# Sheet1.net
KiCad netlist of a schematic drawn in Altium Designer
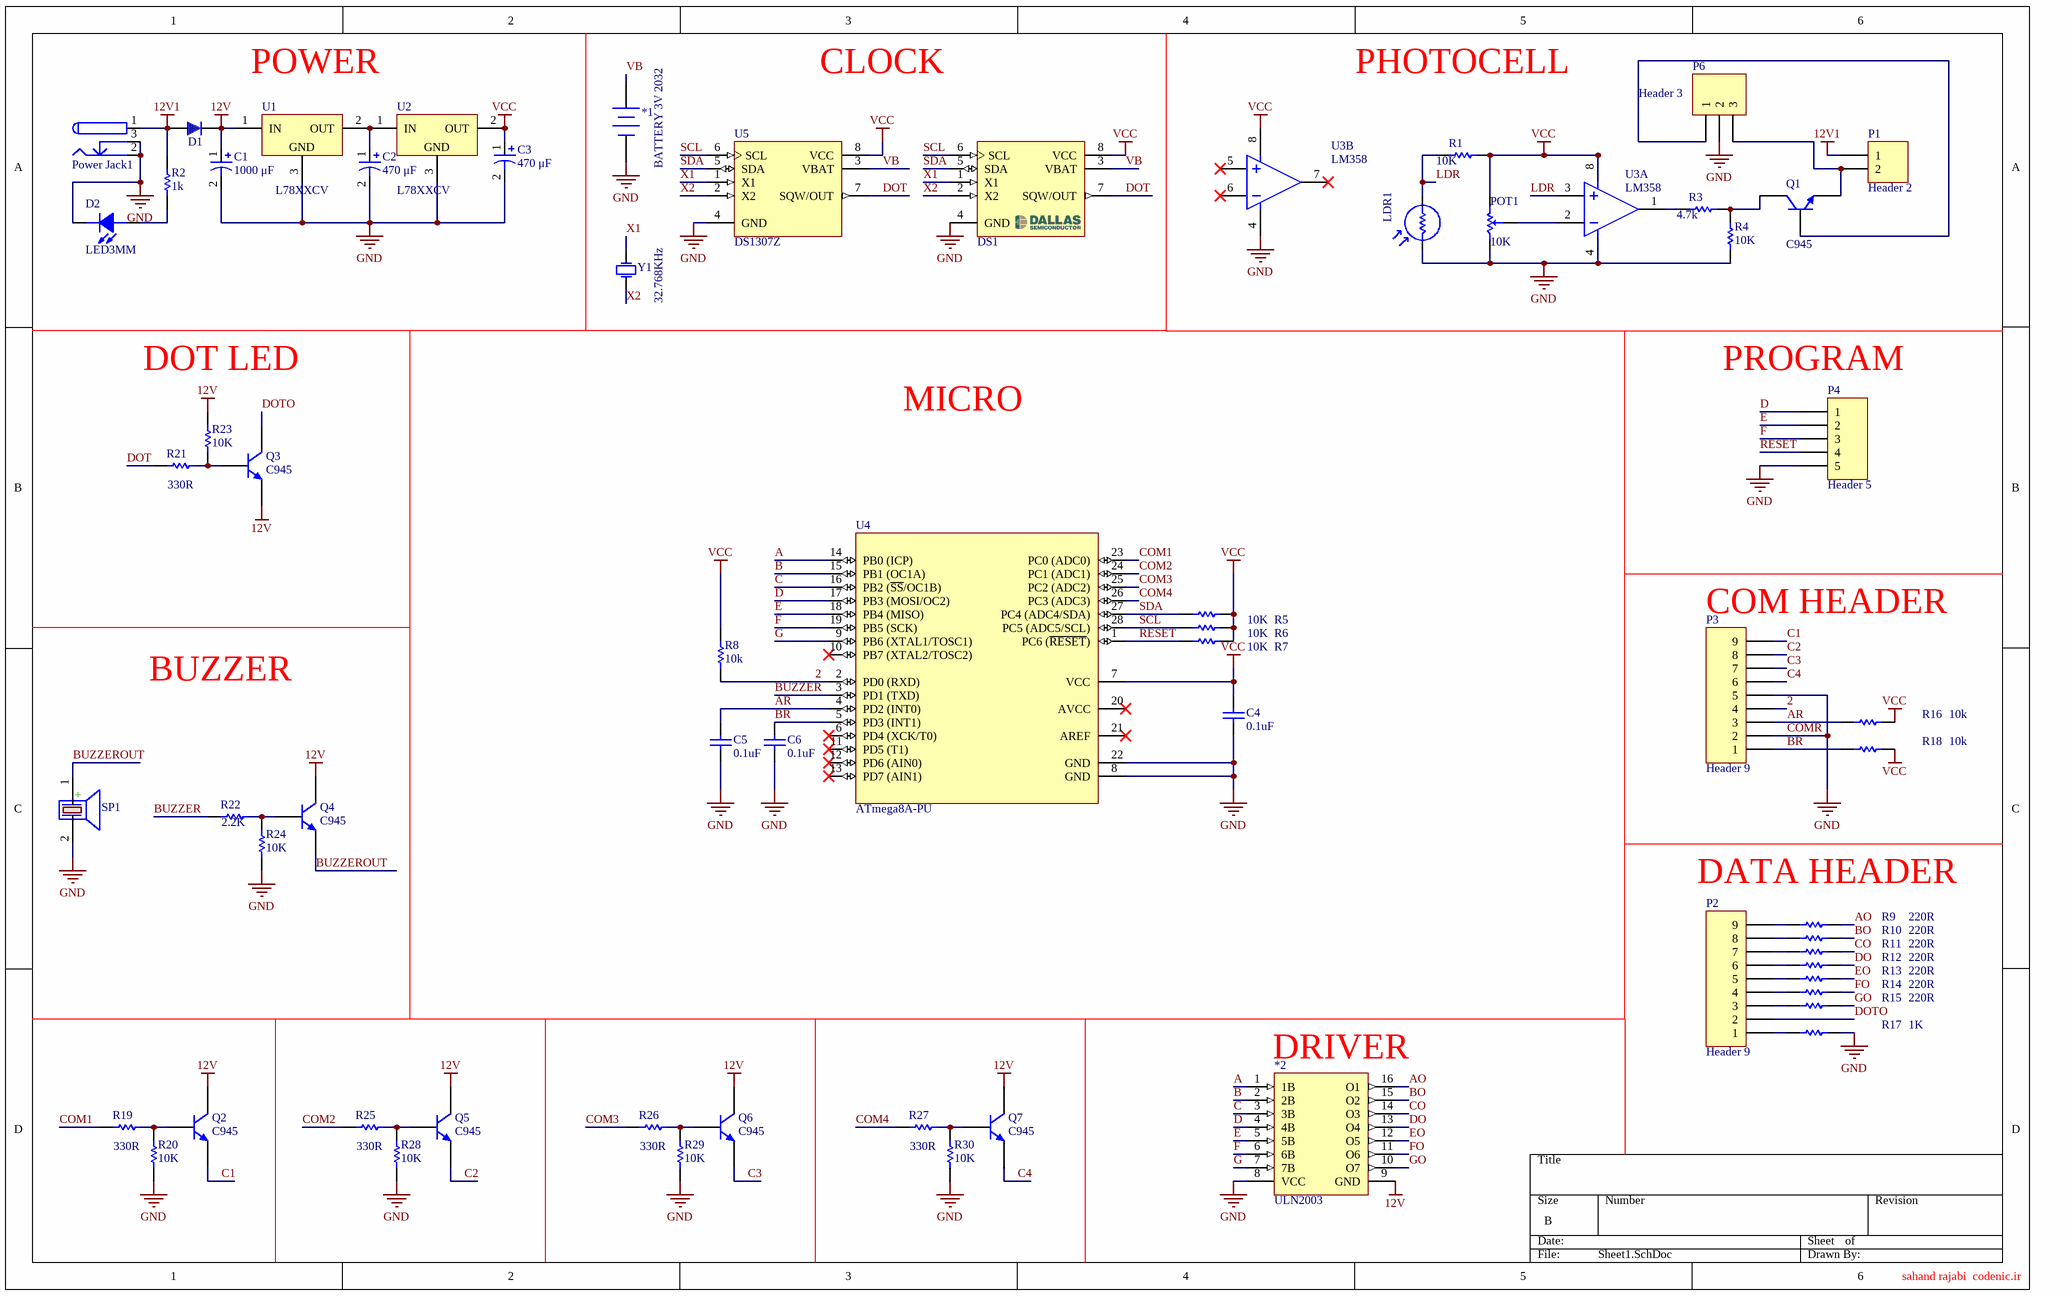
[diagram p0: Sheet1.SchDoc]

(export (version "E")
  (design (tool "Eeschema 10.0.6"))
  (components
    (comp (ref "*1")
      (value "BATTERY 3V 2032")
      (footprint "batt")
      (libsource (lib "General_04") (part "BATTERY 3V 2032"))
    )
    (comp (ref "*2") (value "ULN2003") (footprint "ULN2003") (libsource (lib "General_04") (part "ULN2003")))
    (comp (ref "C1")
      (value "1000 μF")
      (footprint "WCAP-PTHT 8x11.5x3.5x0.6")
      (description "WCAP-PTHT Aluminum Polymer Capacitors , 1000 μF; + / - 20%; 6,3 V , 8 x 11,5")
      (fields
        (field (name "MANUFACTURER") "Wurth Elektronik")
        (field (name "PARTNO") "870135174006")
        (field (name "E-MAIL") "libraries@we-online.com")
        (field (name "CREATED BY") "Karrer Zheng")
      )
      (libsource (lib "Capacitor_13 WCAP-PTHT_rev15a") (part "WCAP-PTHT 8x11.5x3.5x0.6 870135174006"))
    )
    (comp (ref "C2")
      (value "470 μF")
      (footprint "WCAP-PTHT 8x8x3.5x0.6")
      (description "WCAP-PTHT Aluminum Polymer Capacitors , 470 μF; + / - 20%; 6,3 V , 8 x 8")
      (fields
        (field (name "MANUFACTURER") "Wurth Elektronik")
        (field (name "PARTNO") "870135174002")
        (field (name "E-MAIL") "libraries@we-online.com")
        (field (name "CREATED BY") "Karrer Zheng")
      )
      (libsource (lib "Capacitor_13 WCAP-PTHT_rev15a") (part "WCAP-PTHT 8x8x3.5x0.6 870135174002"))
    )
    (comp (ref "C3")
      (value "470 μF")
      (footprint "WCAP-PTHT 8x8x3.5x0.6")
      (description "WCAP-PTHT Aluminum Polymer Capacitors , 470 μF; + / - 20%; 6,3 V , 8 x 8")
      (fields
        (field (name "MANUFACTURER") "Wurth Elektronik")
        (field (name "PARTNO") "870135174002")
        (field (name "E-MAIL") "libraries@we-online.com")
        (field (name "CREATED BY") "Karrer Zheng")
      )
      (libsource (lib "Capacitor_13 WCAP-PTHT_rev15a") (part "WCAP-PTHT 8x8x3.5x0.6 870135174002"))
    )
    (comp (ref "C4")
      (value "0.1uF")
      (footprint "CAPC4817X12N")
      (description "CAP 1206")
      (fields (field (name "DESIGNER") "Abbas Basereh"))
      (libsource (lib "Altium") (part "CAP SMD 1206"))
    )
    (comp (ref "C5")
      (value "0.1uF")
      (footprint "CAPC4817X12N")
      (description "CAP 1206")
      (fields (field (name "DESIGNER") "Abbas Basereh"))
      (libsource (lib "Altium") (part "CAP SMD 1206"))
    )
    (comp (ref "C6")
      (value "0.1uF")
      (footprint "CAPC4817X12N")
      (description "CAP 1206")
      (fields (field (name "DESIGNER") "Abbas Basereh"))
      (libsource (lib "Altium") (part "CAP SMD 1206"))
    )
    (comp (ref "D1")
      (value "1n4007")
      (footprint "DIOM4629X24N")
      (description "Standard Rectifiers")
      (fields (field (name "MANUFACTURER") "DC COMPONENTS") (field (name "DESIGNER") "Abbas Basereh"))
      (libsource (lib "Altium") (part "1n4007 SMD M7"))
    )
    (comp (ref "D2")
      (value "LED3MM")
      (footprint "LED3mm_GRN")
      (description "Light Emitting Diode")
      (fields (field (name "DESIGNER") "Ali Hafizi"))
      (libsource (lib "Altium") (part "LED 3MM"))
    )
    (comp (ref "DS1")
      (value "DS1307")
      (footprint "DIP_8")
      (fields (field (name "PUBLISHER") "Altium Limited"))
      (libsource (lib "General_10") (part "DS1307."))
    )
    (comp (ref "LDR1")
      (value "PhotoCell")
      (footprint "PhotoCell")
      (description "Photo Cell- Variable Resistor With Light")
      (fields (field (name "DESIGNER") "Saeid Jorablo"))
      (libsource (lib "Altium") (part "LDR"))
    )
    (comp (ref "P1")
      (value "Header 2")
      (footprint "HDR1X2")
      (description "Header, 2-Pin")
      (fields (field (name "PUBLISHER") "Altium Limited"))
      (libsource (lib "Altium") (part "Header 2"))
    )
    (comp (ref "P2")
      (value "Header 9")
      (footprint "HDR1X9")
      (description "Header, 9-Pin")
      (fields (field (name "PUBLISHER") "Altium Limited"))
      (libsource (lib "Altium") (part "Header 9"))
    )
    (comp (ref "P3")
      (value "Header 9")
      (footprint "HDR1X9")
      (description "Header, 9-Pin")
      (fields (field (name "PUBLISHER") "Altium Limited"))
      (libsource (lib "Altium") (part "Header 9"))
    )
    (comp (ref "P4")
      (value "Header 5")
      (footprint "HDR1X5")
      (description "Header, 5-Pin")
      (fields (field (name "PUBLISHER") "Altium Limited"))
      (libsource (lib "Altium") (part "Header 5"))
    )
    (comp (ref "P6")
      (value "Header 3")
      (footprint "HDR1X3")
      (description "Header, 3-Pin")
      (fields (field (name "PUBLISHER") "Altium Limited"))
      (libsource (lib "Miscellaneous Connectors") (part "Header 3"))
    )
    (comp (ref "POT1")
      (value "10K")
      (footprint "POT 4")
      (description "Variable Resistor")
      (libsource (lib "Altium") (part "POT"))
    )
    (comp (ref "Power Jack1")
      (value "Power Jack.")
      (footprint "Power Jack.")
      (libsource (lib "General_10") (part "Power Jack."))
    )
    (comp (ref "Q1")
      (value "C945")
      (footprint "c945")
      (description "NPN Silicon Epitaxial Planar Transistor")
      (fields (field (name "PUBLISHER") "Abbas Basereh"))
      (libsource (lib "Altium") (part "C945"))
    )
    (comp (ref "Q2")
      (value "C945")
      (footprint "C945")
      (description "NPN Transistor")
      (fields (field (name "DESIGNER") "Saeid Jorablo"))
      (libsource (lib "My Library1111") (part "C945"))
    )
    (comp (ref "Q3")
      (value "C945")
      (footprint "C945")
      (description "NPN Transistor")
      (fields (field (name "DESIGNER") "Saeid Jorablo"))
      (libsource (lib "My Library1111") (part "C945"))
    )
    (comp (ref "Q4")
      (value "C945")
      (footprint "C945")
      (description "NPN Transistor")
      (fields (field (name "DESIGNER") "Saeid Jorablo"))
      (libsource (lib "My Library1111") (part "C945"))
    )
    (comp (ref "Q5")
      (value "C945")
      (footprint "C945")
      (description "NPN Transistor")
      (fields (field (name "DESIGNER") "Saeid Jorablo"))
      (libsource (lib "My Library1111") (part "C945"))
    )
    (comp (ref "Q6")
      (value "C945")
      (footprint "C945")
      (description "NPN Transistor")
      (fields (field (name "DESIGNER") "Saeid Jorablo"))
      (libsource (lib "My Library1111") (part "C945"))
    )
    (comp (ref "Q7")
      (value "C945")
      (footprint "C945")
      (description "NPN Transistor")
      (fields (field (name "DESIGNER") "Saeid Jorablo"))
      (libsource (lib "My Library1111") (part "C945"))
    )
    (comp (ref "R1")
      (value "10K")
      (footprint "Resistor_SMD_1206")
      (description "Resistor 0.25w")
      (fields (field (name "PUBLISHER") "Altium Limited"))
      (libsource (lib "General_10") (part "Resistor"))
    )
    (comp (ref "R2")
      (value "1k")
      (footprint "Resistor_SMD_1206")
      (description "Resistor 0.25w")
      (fields (field (name "PUBLISHER") "Altium Limited"))
      (libsource (lib "General_10") (part "Resistor"))
    )
    (comp (ref "R3")
      (value "4.7k")
      (footprint "Resistor_SMD_1206")
      (description "Resistor 0.25w")
      (fields (field (name "PUBLISHER") "Altium Limited"))
      (libsource (lib "General_10") (part "Resistor"))
    )
    (comp (ref "R4")
      (value "10K")
      (footprint "Resistor_SMD_1206")
      (description "Resistor 0.25w")
      (fields (field (name "PUBLISHER") "Altium Limited"))
      (libsource (lib "General_10") (part "Resistor"))
    )
    (comp (ref "R5")
      (value "10K")
      (footprint "Resistor_SMD_1206")
      (description "Resistor 0.25w")
      (fields (field (name "PUBLISHER") "Altium Limited"))
      (libsource (lib "General_10") (part "Resistor"))
    )
    (comp (ref "R6")
      (value "10K")
      (footprint "Resistor_SMD_1206")
      (description "Resistor 0.25w")
      (fields (field (name "PUBLISHER") "Altium Limited"))
      (libsource (lib "General_10") (part "Resistor"))
    )
    (comp (ref "R7")
      (value "10K")
      (footprint "Resistor_SMD_1206")
      (description "Resistor 0.25w")
      (fields (field (name "PUBLISHER") "Altium Limited"))
      (libsource (lib "General_10") (part "Resistor"))
    )
    (comp (ref "R8")
      (value "10k")
      (footprint "Resistor_SMD_1206")
      (description "Resistor 0.25w")
      (fields (field (name "PUBLISHER") "Altium Limited"))
      (libsource (lib "General_10") (part "Resistor"))
    )
    (comp (ref "R9")
      (value "220R")
      (footprint "Resistor_SMD_1206")
      (description "Resistor 0.25w")
      (fields (field (name "PUBLISHER") "Altium Limited"))
      (libsource (lib "General_10") (part "Resistor"))
    )
    (comp (ref "R10")
      (value "220R")
      (footprint "Resistor_SMD_1206")
      (description "Resistor 0.25w")
      (fields (field (name "PUBLISHER") "Altium Limited"))
      (libsource (lib "General_10") (part "Resistor"))
    )
    (comp (ref "R11")
      (value "220R")
      (footprint "Resistor_SMD_1206")
      (description "Resistor 0.25w")
      (fields (field (name "PUBLISHER") "Altium Limited"))
      (libsource (lib "General_10") (part "Resistor"))
    )
    (comp (ref "R12")
      (value "220R")
      (footprint "Resistor_SMD_1206")
      (description "Resistor 0.25w")
      (fields (field (name "PUBLISHER") "Altium Limited"))
      (libsource (lib "General_10") (part "Resistor"))
    )
    (comp (ref "R13")
      (value "220R")
      (footprint "Resistor_SMD_1206")
      (description "Resistor 0.25w")
      (fields (field (name "PUBLISHER") "Altium Limited"))
      (libsource (lib "General_10") (part "Resistor"))
    )
    (comp (ref "R14")
      (value "220R")
      (footprint "Resistor_SMD_1206")
      (description "Resistor 0.25w")
      (fields (field (name "PUBLISHER") "Altium Limited"))
      (libsource (lib "General_10") (part "Resistor"))
    )
    (comp (ref "R15")
      (value "220R")
      (footprint "Resistor_SMD_1206")
      (description "Resistor 0.25w")
      (fields (field (name "PUBLISHER") "Altium Limited"))
      (libsource (lib "General_10") (part "Resistor"))
    )
    (comp (ref "R16")
      (value "10k")
      (footprint "Resistor_SMD_1206")
      (description "Resistor 0.25w")
      (fields (field (name "PUBLISHER") "Altium Limited"))
      (libsource (lib "General_10") (part "Resistor"))
    )
    (comp (ref "R17")
      (value "1K")
      (footprint "Resistor_SMD_1206")
      (description "Resistor 0.25w")
      (fields (field (name "PUBLISHER") "Altium Limited"))
      (libsource (lib "General_10") (part "Resistor"))
    )
    (comp (ref "R18")
      (value "10k")
      (footprint "Resistor_SMD_1206")
      (description "Resistor 0.25w")
      (fields (field (name "PUBLISHER") "Altium Limited"))
      (libsource (lib "General_10") (part "Resistor"))
    )
    (comp (ref "R19")
      (value "330R")
      (footprint "RESC3413X04N")
      (description "RES 0805")
      (fields (field (name "DESIGNER") "Abbas Basereh"))
      (libsource (lib "2017AbbasBasereh9365731239 -ver1") (part "RES 0805 0.125W"))
    )
    (comp (ref "R20")
      (value "10K")
      (footprint "RESC3413X04N")
      (description "RES 0805")
      (fields (field (name "DESIGNER") "Abbas Basereh"))
      (libsource (lib "2017AbbasBasereh9365731239 -ver1") (part "RES 0805 0.125W"))
    )
    (comp (ref "R21")
      (value "330R")
      (footprint "RESC3413X04N")
      (description "RES 0805")
      (fields (field (name "DESIGNER") "Abbas Basereh"))
      (libsource (lib "2017AbbasBasereh9365731239 -ver1") (part "RES 0805 0.125W"))
    )
    (comp (ref "R22")
      (value "2.2K")
      (footprint "RESC3413X04N")
      (description "RES 0805")
      (fields (field (name "DESIGNER") "Abbas Basereh"))
      (libsource (lib "2017AbbasBasereh9365731239 -ver1") (part "RES 0805 0.125W"))
    )
    (comp (ref "R23")
      (value "10K")
      (footprint "RESC3413X04N")
      (description "RES 0805")
      (fields (field (name "DESIGNER") "Abbas Basereh"))
      (libsource (lib "2017AbbasBasereh9365731239 -ver1") (part "RES 0805 0.125W"))
    )
    (comp (ref "R24")
      (value "10K")
      (footprint "RESC3413X04N")
      (description "RES 0805")
      (fields (field (name "DESIGNER") "Abbas Basereh"))
      (libsource (lib "2017AbbasBasereh9365731239 -ver1") (part "RES 0805 0.125W"))
    )
    (comp (ref "R25")
      (value "330R")
      (footprint "RESC3413X04N")
      (description "RES 0805")
      (fields (field (name "DESIGNER") "Abbas Basereh"))
      (libsource (lib "2017AbbasBasereh9365731239 -ver1") (part "RES 0805 0.125W"))
    )
    (comp (ref "R26")
      (value "330R")
      (footprint "RESC3413X04N")
      (description "RES 0805")
      (fields (field (name "DESIGNER") "Abbas Basereh"))
      (libsource (lib "2017AbbasBasereh9365731239 -ver1") (part "RES 0805 0.125W"))
    )
    (comp (ref "R27")
      (value "330R")
      (footprint "RESC3413X04N")
      (description "RES 0805")
      (fields (field (name "DESIGNER") "Abbas Basereh"))
      (libsource (lib "2017AbbasBasereh9365731239 -ver1") (part "RES 0805 0.125W"))
    )
    (comp (ref "R28")
      (value "10K")
      (footprint "RESC3413X04N")
      (description "RES 0805")
      (fields (field (name "DESIGNER") "Abbas Basereh"))
      (libsource (lib "2017AbbasBasereh9365731239 -ver1") (part "RES 0805 0.125W"))
    )
    (comp (ref "R29")
      (value "10K")
      (footprint "RESC3413X04N")
      (description "RES 0805")
      (fields (field (name "DESIGNER") "Abbas Basereh"))
      (libsource (lib "2017AbbasBasereh9365731239 -ver1") (part "RES 0805 0.125W"))
    )
    (comp (ref "R30")
      (value "10K")
      (footprint "RESC3413X04N")
      (description "RES 0805")
      (fields (field (name "DESIGNER") "Abbas Basereh"))
      (libsource (lib "2017AbbasBasereh9365731239 -ver1") (part "RES 0805 0.125W"))
    )
    (comp (ref "SP1")
      (value "~")
      (footprint "BUZZER 7.62mm DC")
      (description "PIEZO BUZZER ACTIVE")
      (fields (field (name "DESIGNER") "Abbas Basereh") (field (name "PUBLISHER") "Abbas Basereh"))
      (libsource (lib "Altium") (part "PIEZO BUZZER"))
    )
    (comp (ref "U1")
      (value "L78XXCV")
      (footprint "78XXCV - Right")
      (description "Fixed Voltage Regulator")
      (fields (field (name "DESIGNER") "Saeid Jorablo"))
      (libsource (lib "Altium") (part "L78XXCV"))
    )
    (comp (ref "U2")
      (value "L78XXCV")
      (footprint "78XXCV - Right")
      (description "Fixed Voltage Regulator")
      (fields (field (name "DESIGNER") "Saeid Jorablo"))
      (libsource (lib "Altium") (part "L78XXCV"))
    )
    (comp (ref "U3")
      (value "LM358")
      (footprint "DIP8E")
      (libsource (lib "Protel DOS Schematic") (part "1458"))
    )
    (comp (ref "U4")
      (value "ATmega8A-PU")
      (footprint "28P3")
      (fields (field (name "PUBLISHER") "Abbas Basereh"))
      (libsource (lib "Altium") (part "ATmega8A-PU"))
    )
    (comp (ref "U5")
      (value "DS1307Z")
      (footprint "SOIC8N_N")
      (description "64 X 8 Serial Real-Time Clock")
      (fields (field (name "PUBLISHER") "Altium Limited"))
      (libsource (lib "Dallas Peripheral Real Time Clock") (part "DS1307Z"))
    )
    (comp (ref "Y1")
      (value "32.768KHz")
      (footprint "XTAL RTC")
      (description "XTAL Crystal")
      (fields (field (name "DESIGNER") "ABBAS BASEREH"))
      (libsource (lib "Altium") (part "XTAL"))
    )
  )
  (nets
    (net (code "1") (name "/2") (class "Default")
      (node (ref "P3") (pin "4") (pinfunction "4_4") (pintype "passive"))
      (node (ref "R8") (pin "1") (pinfunction "1_1") (pintype "passive"))
      (node (ref "U4") (pin "2") (pinfunction "PD0_(RXD)_2") (pintype "bidirectional"))
    )
    (net (code "2") (name "/A") (class "Default")
      (node (ref "*2") (pin "1") (pinfunction "1B_1") (pintype "input"))
      (node (ref "U4") (pin "14") (pinfunction "PB0_(ICP)_14") (pintype "bidirectional"))
    )
    (net (code "3") (name "/AO") (class "Default")
      (node (ref "*2") (pin "16") (pinfunction "O1_16") (pintype "output"))
      (node (ref "R9") (pin "2") (pinfunction "2_2") (pintype "passive"))
    )
    (net (code "4") (name "/AR") (class "Default")
      (node (ref "C5") (pin "2") (pinfunction "2_2") (pintype "passive"))
      (node (ref "P3") (pin "3") (pinfunction "3_3") (pintype "passive"))
      (node (ref "R16") (pin "1") (pinfunction "1_1") (pintype "passive"))
      (node (ref "U4") (pin "4") (pinfunction "PD2_(INT0)_4") (pintype "bidirectional"))
    )
    (net (code "5") (name "/B") (class "Default")
      (node (ref "*2") (pin "2") (pinfunction "2B_2") (pintype "input"))
      (node (ref "U4") (pin "15") (pinfunction "PB1_(OC1A)_15") (pintype "bidirectional"))
    )
    (net (code "6") (name "/BO") (class "Default")
      (node (ref "*2") (pin "15") (pinfunction "O2_15") (pintype "output"))
      (node (ref "R10") (pin "2") (pinfunction "2_2") (pintype "passive"))
    )
    (net (code "7") (name "/BR") (class "Default")
      (node (ref "C6") (pin "2") (pinfunction "2_2") (pintype "passive"))
      (node (ref "P3") (pin "1") (pinfunction "1_1") (pintype "passive"))
      (node (ref "R18") (pin "1") (pinfunction "1_1") (pintype "passive"))
      (node (ref "U4") (pin "5") (pinfunction "PD3_(INT1)_5") (pintype "bidirectional"))
    )
    (net (code "8") (name "/BUZZER") (class "Default")
      (node (ref "R22") (pin "1") (pinfunction "1_1") (pintype "passive"))
      (node (ref "U4") (pin "3") (pinfunction "PD1_(TXD)_3") (pintype "bidirectional"))
    )
    (net (code "9") (name "/BUZZEROUT") (class "Default")
      (node (ref "Q4") (pin "1") (pinfunction "E_1") (pintype "passive"))
      (node (ref "SP1") (pin "1") (pinfunction "+_1") (pintype "passive"))
    )
    (net (code "10") (name "/C") (class "Default")
      (node (ref "*2") (pin "3") (pinfunction "3B_3") (pintype "input"))
      (node (ref "U4") (pin "16") (pinfunction "PB2_(~{SS}/OC1B)_16") (pintype "bidirectional"))
    )
    (net (code "11") (name "/C1") (class "Default")
      (node (ref "P3") (pin "9") (pinfunction "9_9") (pintype "passive"))
      (node (ref "Q2") (pin "1") (pinfunction "E_1") (pintype "passive"))
    )
    (net (code "12") (name "/C2") (class "Default")
      (node (ref "P3") (pin "8") (pinfunction "8_8") (pintype "passive"))
      (node (ref "Q5") (pin "1") (pinfunction "E_1") (pintype "passive"))
    )
    (net (code "13") (name "/C3") (class "Default")
      (node (ref "P3") (pin "7") (pinfunction "7_7") (pintype "passive"))
      (node (ref "Q6") (pin "1") (pinfunction "E_1") (pintype "passive"))
    )
    (net (code "14") (name "/C4") (class "Default")
      (node (ref "P3") (pin "6") (pinfunction "6_6") (pintype "passive"))
      (node (ref "Q7") (pin "1") (pinfunction "E_1") (pintype "passive"))
    )
    (net (code "15") (name "/CO") (class "Default")
      (node (ref "*2") (pin "14") (pinfunction "O3_14") (pintype "output"))
      (node (ref "R11") (pin "2") (pinfunction "2_2") (pintype "passive"))
    )
    (net (code "16") (name "/COM1") (class "Default")
      (node (ref "R19") (pin "1") (pinfunction "1_1") (pintype "passive"))
      (node (ref "U4") (pin "23") (pinfunction "PC0_(ADC0)_23") (pintype "bidirectional"))
    )
    (net (code "17") (name "/COM2") (class "Default")
      (node (ref "R25") (pin "1") (pinfunction "1_1") (pintype "passive"))
      (node (ref "U4") (pin "24") (pinfunction "PC1_(ADC1)_24") (pintype "bidirectional"))
    )
    (net (code "18") (name "/COM3") (class "Default")
      (node (ref "R26") (pin "1") (pinfunction "1_1") (pintype "passive"))
      (node (ref "U4") (pin "25") (pinfunction "PC2_(ADC2)_25") (pintype "bidirectional"))
    )
    (net (code "19") (name "/COM4") (class "Default")
      (node (ref "R27") (pin "1") (pinfunction "1_1") (pintype "passive"))
      (node (ref "U4") (pin "26") (pinfunction "PC3_(ADC3)_26") (pintype "bidirectional"))
    )
    (net (code "20") (name "/D") (class "Default")
      (node (ref "*2") (pin "4") (pinfunction "4B_4") (pintype "input"))
      (node (ref "P4") (pin "1") (pinfunction "1_1") (pintype "passive"))
      (node (ref "U4") (pin "17") (pinfunction "PB3_(MOSI/OC2)_17") (pintype "bidirectional"))
    )
    (net (code "21") (name "/DO") (class "Default")
      (node (ref "*2") (pin "13") (pinfunction "O4_13") (pintype "output"))
      (node (ref "R12") (pin "2") (pinfunction "2_2") (pintype "passive"))
    )
    (net (code "22") (name "/DOT") (class "Default")
      (node (ref "DS1") (pin "7") (pinfunction "SQW/OUT_7") (pintype "output"))
      (node (ref "R21") (pin "1") (pinfunction "1_1") (pintype "passive"))
      (node (ref "U5") (pin "7") (pinfunction "SQW/OUT_7") (pintype "output"))
    )
    (net (code "23") (name "/DOTO") (class "Default")
      (node (ref "P2") (pin "2") (pinfunction "2_2") (pintype "passive"))
      (node (ref "Q3") (pin "2") (pinfunction "C_2") (pintype "passive"))
    )
    (net (code "24") (name "/E") (class "Default")
      (node (ref "*2") (pin "5") (pinfunction "5B_5") (pintype "input"))
      (node (ref "P4") (pin "2") (pinfunction "2_2") (pintype "passive"))
      (node (ref "U4") (pin "18") (pinfunction "PB4_(MISO)_18") (pintype "bidirectional"))
    )
    (net (code "25") (name "/EO") (class "Default")
      (node (ref "*2") (pin "12") (pinfunction "O5_12") (pintype "output"))
      (node (ref "R13") (pin "2") (pinfunction "2_2") (pintype "passive"))
    )
    (net (code "26") (name "/F") (class "Default")
      (node (ref "*2") (pin "6") (pinfunction "6B_6") (pintype "input"))
      (node (ref "P4") (pin "3") (pinfunction "3_3") (pintype "passive"))
      (node (ref "U4") (pin "19") (pinfunction "PB5_(SCK)_19") (pintype "bidirectional"))
    )
    (net (code "27") (name "/FO") (class "Default")
      (node (ref "*2") (pin "11") (pinfunction "O6_11") (pintype "output"))
      (node (ref "R14") (pin "2") (pinfunction "2_2") (pintype "passive"))
    )
    (net (code "28") (name "/G") (class "Default")
      (node (ref "*2") (pin "7") (pinfunction "7B_7") (pintype "input"))
      (node (ref "U4") (pin "9") (pinfunction "PB6_(XTAL1/TOSC1)_9") (pintype "bidirectional"))
    )
    (net (code "29") (name "/GO") (class "Default")
      (node (ref "*2") (pin "10") (pinfunction "O7_10") (pintype "output"))
      (node (ref "R15") (pin "2") (pinfunction "2_2") (pintype "passive"))
    )
    (net (code "30") (name "/LDR") (class "Default")
      (node (ref "LDR1") (pin "2") (pintype "passive"))
      (node (ref "R1") (pin "1") (pinfunction "1_1") (pintype "passive"))
      (node (ref "U3") (pin "3") (pintype "passive"))
    )
    (net (code "31") (name "/RESET") (class "Default")
      (node (ref "P4") (pin "4") (pinfunction "4_4") (pintype "passive"))
      (node (ref "R7") (pin "1") (pinfunction "1_1") (pintype "passive"))
      (node (ref "U4") (pin "1") (pinfunction "PC6_(~{RESET})_1") (pintype "bidirectional"))
    )
    (net (code "32") (name "/SCL") (class "Default")
      (node (ref "DS1") (pin "6") (pinfunction "SCL_6") (pintype "input"))
      (node (ref "R6") (pin "1") (pinfunction "1_1") (pintype "passive"))
      (node (ref "U4") (pin "28") (pinfunction "PC5_(ADC5/SCL)_28") (pintype "bidirectional"))
      (node (ref "U5") (pin "6") (pinfunction "SCL_6") (pintype "input"))
    )
    (net (code "33") (name "/SDA") (class "Default")
      (node (ref "DS1") (pin "5") (pinfunction "SDA_5") (pintype "bidirectional"))
      (node (ref "R5") (pin "1") (pinfunction "1_1") (pintype "passive"))
      (node (ref "U4") (pin "27") (pinfunction "PC4_(ADC4/SDA)_27") (pintype "bidirectional"))
      (node (ref "U5") (pin "5") (pinfunction "SDA_5") (pintype "bidirectional"))
    )
    (net (code "34") (name "/VB") (class "Default")
      (node (ref "*1") (pin "1") (pinfunction "+_1") (pintype "passive"))
      (node (ref "DS1") (pin "3") (pinfunction "VBAT_3") (pintype "power_in"))
      (node (ref "U5") (pin "3") (pinfunction "VBAT_3") (pintype "power_in"))
    )
    (net (code "35") (name "/X1") (class "Default")
      (node (ref "DS1") (pin "1") (pinfunction "X1_1") (pintype "input"))
      (node (ref "U5") (pin "1") (pinfunction "X1_1") (pintype "input"))
      (node (ref "Y1") (pin "2") (pinfunction "OSC2_2") (pintype "passive"))
    )
    (net (code "36") (name "/X2") (class "Default")
      (node (ref "DS1") (pin "2") (pinfunction "X2_2") (pintype "input"))
      (node (ref "U5") (pin "2") (pinfunction "X2_2") (pintype "input"))
      (node (ref "Y1") (pin "1") (pinfunction "OSC1_1") (pintype "passive"))
    )
    (net (code "37") (name "12V") (class "Default")
      (node (ref "*2") (pin "9") (pinfunction "GND_9") (pintype "passive"))
      (node (ref "C1") (pin "1") (pinfunction "1_1") (pintype "passive"))
      (node (ref "D1") (pin "2") (pintype "passive"))
      (node (ref "Q2") (pin "2") (pinfunction "C_2") (pintype "passive"))
      (node (ref "Q3") (pin "1") (pinfunction "E_1") (pintype "passive"))
      (node (ref "Q4") (pin "2") (pinfunction "C_2") (pintype "passive"))
      (node (ref "Q5") (pin "2") (pinfunction "C_2") (pintype "passive"))
      (node (ref "Q6") (pin "2") (pinfunction "C_2") (pintype "passive"))
      (node (ref "Q7") (pin "2") (pinfunction "C_2") (pintype "passive"))
      (node (ref "R23") (pin "1") (pinfunction "1_1") (pintype "passive"))
      (node (ref "U1") (pin "1") (pinfunction "IN_1") (pintype "passive"))
    )
    (net (code "38") (name "12V1") (class "Default")
      (node (ref "D1") (pin "1") (pintype "passive"))
      (node (ref "P1") (pin "1") (pinfunction "1_1") (pintype "passive"))
      (node (ref "Power Jack1") (pin "1") (pinfunction "1_1") (pintype "power_in"))
      (node (ref "R2") (pin "2") (pinfunction "2_2") (pintype "passive"))
    )
    (net (code "39") (name "GND") (class "Default")
      (node (ref "*1") (pin "2") (pinfunction "-_2") (pintype "passive"))
      (node (ref "*2") (pin "8") (pinfunction "VCC_8") (pintype "passive"))
      (node (ref "C1") (pin "2") (pinfunction "2_2") (pintype "passive"))
      (node (ref "C2") (pin "2") (pinfunction "2_2") (pintype "passive"))
      (node (ref "C3") (pin "2") (pinfunction "2_2") (pintype "passive"))
      (node (ref "C4") (pin "1") (pinfunction "1_1") (pintype "passive"))
      (node (ref "C5") (pin "1") (pinfunction "1_1") (pintype "passive"))
      (node (ref "C6") (pin "1") (pinfunction "1_1") (pintype "passive"))
      (node (ref "D2") (pin "2") (pinfunction "CATHODE_2") (pintype "passive"))
      (node (ref "DS1") (pin "4") (pinfunction "GND_4") (pintype "power_in"))
      (node (ref "LDR1") (pin "1") (pintype "passive"))
      (node (ref "P3") (pin "2") (pinfunction "2_2") (pintype "passive"))
      (node (ref "P3") (pin "5") (pinfunction "5_5") (pintype "passive"))
      (node (ref "P4") (pin "5") (pinfunction "5_5") (pintype "passive"))
      (node (ref "P6") (pin "2") (pinfunction "2_2") (pintype "passive"))
      (node (ref "POT1") (pin "1") (pinfunction "CCW_1") (pintype "passive"))
      (node (ref "Power Jack1") (pin "2") (pinfunction "2_2") (pintype "power_in"))
      (node (ref "Power Jack1") (pin "3") (pinfunction "3_3") (pintype "power_in"))
      (node (ref "R17") (pin "2") (pinfunction "2_2") (pintype "passive"))
      (node (ref "R20") (pin "1") (pinfunction "1_1") (pintype "passive"))
      (node (ref "R24") (pin "1") (pinfunction "1_1") (pintype "passive"))
      (node (ref "R28") (pin "1") (pinfunction "1_1") (pintype "passive"))
      (node (ref "R29") (pin "1") (pinfunction "1_1") (pintype "passive"))
      (node (ref "R30") (pin "1") (pinfunction "1_1") (pintype "passive"))
      (node (ref "R4") (pin "1") (pinfunction "1_1") (pintype "passive"))
      (node (ref "SP1") (pin "2") (pinfunction "-_2") (pintype "passive"))
      (node (ref "U1") (pin "3") (pinfunction "GND_3") (pintype "passive"))
      (node (ref "U2") (pin "3") (pinfunction "GND_3") (pintype "passive"))
      (node (ref "U3") (pin "4") (pintype "passive"))
      (node (ref "U4") (pin "22") (pinfunction "GND_22") (pintype "power_in"))
      (node (ref "U4") (pin "8") (pinfunction "GND_8") (pintype "power_in"))
      (node (ref "U5") (pin "4") (pinfunction "GND_4") (pintype "power_in"))
    )
    (net (code "40") (name "Net-(D2-ANODE)") (class "Default")
      (node (ref "D2") (pin "1") (pinfunction "ANODE_1") (pintype "passive"))
      (node (ref "R2") (pin "1") (pinfunction "1_1") (pintype "passive"))
    )
    (net (code "41") (name "Net-(P2-Pad1)") (class "Default")
      (node (ref "P2") (pin "1") (pinfunction "1_1") (pintype "passive"))
      (node (ref "R17") (pin "1") (pinfunction "1_1") (pintype "passive"))
    )
    (net (code "42") (name "Net-(P2-Pad3)") (class "Default")
      (node (ref "P2") (pin "3") (pinfunction "3_3") (pintype "passive"))
      (node (ref "R15") (pin "1") (pinfunction "1_1") (pintype "passive"))
    )
    (net (code "43") (name "Net-(P2-Pad4)") (class "Default")
      (node (ref "P2") (pin "4") (pinfunction "4_4") (pintype "passive"))
      (node (ref "R14") (pin "1") (pinfunction "1_1") (pintype "passive"))
    )
    (net (code "44") (name "Net-(P2-Pad5)") (class "Default")
      (node (ref "P2") (pin "5") (pinfunction "5_5") (pintype "passive"))
      (node (ref "R13") (pin "1") (pinfunction "1_1") (pintype "passive"))
    )
    (net (code "45") (name "Net-(P2-Pad6)") (class "Default")
      (node (ref "P2") (pin "6") (pinfunction "6_6") (pintype "passive"))
      (node (ref "R12") (pin "1") (pinfunction "1_1") (pintype "passive"))
    )
    (net (code "46") (name "Net-(P2-Pad7)") (class "Default")
      (node (ref "P2") (pin "7") (pinfunction "7_7") (pintype "passive"))
      (node (ref "R11") (pin "1") (pinfunction "1_1") (pintype "passive"))
    )
    (net (code "47") (name "Net-(P2-Pad8)") (class "Default")
      (node (ref "P2") (pin "8") (pinfunction "8_8") (pintype "passive"))
      (node (ref "R10") (pin "1") (pinfunction "1_1") (pintype "passive"))
    )
    (net (code "48") (name "Net-(P2-Pad9)") (class "Default")
      (node (ref "P2") (pin "9") (pinfunction "9_9") (pintype "passive"))
      (node (ref "R9") (pin "1") (pinfunction "1_1") (pintype "passive"))
    )
    (net (code "49") (name "Net-(POT1-SetPoint)") (class "Default")
      (node (ref "POT1") (pin "3") (pinfunction "SetPoint_3") (pintype "passive"))
      (node (ref "U3") (pin "2") (pintype "passive"))
    )
    (net (code "50") (name "Net-(Q1-B)") (class "Default")
      (node (ref "P6") (pin "1") (pinfunction "1_1") (pintype "passive"))
      (node (ref "Q1") (pin "1") (pinfunction "B_1") (pintype "passive"))
    )
    (net (code "51") (name "Net-(Q1-C)") (class "Default")
      (node (ref "Q1") (pin "3") (pinfunction "C_3") (pintype "passive"))
      (node (ref "R3") (pin "2") (pinfunction "2_2") (pintype "passive"))
      (node (ref "R4") (pin "2") (pinfunction "2_2") (pintype "passive"))
    )
    (net (code "52") (name "Net-(Q1-E)") (class "Default")
      (node (ref "P1") (pin "2") (pinfunction "2_2") (pintype "passive"))
      (node (ref "P6") (pin "3") (pinfunction "3_3") (pintype "passive"))
      (node (ref "Q1") (pin "2") (pinfunction "E_2") (pintype "passive"))
    )
    (net (code "53") (name "Net-(Q2-B)") (class "Default")
      (node (ref "Q2") (pin "3") (pinfunction "B_3") (pintype "passive"))
      (node (ref "R19") (pin "2") (pinfunction "2_2") (pintype "passive"))
      (node (ref "R20") (pin "2") (pinfunction "2_2") (pintype "passive"))
    )
    (net (code "54") (name "Net-(Q3-B)") (class "Default")
      (node (ref "Q3") (pin "3") (pinfunction "B_3") (pintype "passive"))
      (node (ref "R21") (pin "2") (pinfunction "2_2") (pintype "passive"))
      (node (ref "R23") (pin "2") (pinfunction "2_2") (pintype "passive"))
    )
    (net (code "55") (name "Net-(Q4-B)") (class "Default")
      (node (ref "Q4") (pin "3") (pinfunction "B_3") (pintype "passive"))
      (node (ref "R22") (pin "2") (pinfunction "2_2") (pintype "passive"))
      (node (ref "R24") (pin "2") (pinfunction "2_2") (pintype "passive"))
    )
    (net (code "56") (name "Net-(Q5-B)") (class "Default")
      (node (ref "Q5") (pin "3") (pinfunction "B_3") (pintype "passive"))
      (node (ref "R25") (pin "2") (pinfunction "2_2") (pintype "passive"))
      (node (ref "R28") (pin "2") (pinfunction "2_2") (pintype "passive"))
    )
    (net (code "57") (name "Net-(Q6-B)") (class "Default")
      (node (ref "Q6") (pin "3") (pinfunction "B_3") (pintype "passive"))
      (node (ref "R26") (pin "2") (pinfunction "2_2") (pintype "passive"))
      (node (ref "R29") (pin "2") (pinfunction "2_2") (pintype "passive"))
    )
    (net (code "58") (name "Net-(Q7-B)") (class "Default")
      (node (ref "Q7") (pin "3") (pinfunction "B_3") (pintype "passive"))
      (node (ref "R27") (pin "2") (pinfunction "2_2") (pintype "passive"))
      (node (ref "R30") (pin "2") (pinfunction "2_2") (pintype "passive"))
    )
    (net (code "59") (name "Net-(R3-Pad1)") (class "Default")
      (node (ref "R3") (pin "1") (pinfunction "1_1") (pintype "passive"))
      (node (ref "U3") (pin "1") (pintype "passive"))
    )
    (net (code "60") (name "Net-(U1-OUT)") (class "Default")
      (node (ref "C2") (pin "1") (pinfunction "1_1") (pintype "passive"))
      (node (ref "U1") (pin "2") (pinfunction "OUT_2") (pintype "passive"))
      (node (ref "U2") (pin "1") (pinfunction "IN_1") (pintype "passive"))
    )
    (net (code "61") (name "VCC") (class "Default")
      (node (ref "C3") (pin "1") (pinfunction "1_1") (pintype "passive"))
      (node (ref "C4") (pin "2") (pinfunction "2_2") (pintype "passive"))
      (node (ref "DS1") (pin "8") (pinfunction "VCC_8") (pintype "power_in"))
      (node (ref "POT1") (pin "2") (pinfunction "CW_2") (pintype "passive"))
      (node (ref "R1") (pin "2") (pinfunction "2_2") (pintype "passive"))
      (node (ref "R16") (pin "2") (pinfunction "2_2") (pintype "passive"))
      (node (ref "R18") (pin "2") (pinfunction "2_2") (pintype "passive"))
      (node (ref "R5") (pin "2") (pinfunction "2_2") (pintype "passive"))
      (node (ref "R6") (pin "2") (pinfunction "2_2") (pintype "passive"))
      (node (ref "R7") (pin "2") (pinfunction "2_2") (pintype "passive"))
      (node (ref "R8") (pin "2") (pinfunction "2_2") (pintype "passive"))
      (node (ref "U2") (pin "2") (pinfunction "OUT_2") (pintype "passive"))
      (node (ref "U3") (pin "8") (pintype "passive"))
      (node (ref "U4") (pin "7") (pinfunction "VCC_7") (pintype "power_in"))
      (node (ref "U5") (pin "8") (pinfunction "VCC_8") (pintype "power_in"))
    )
    (net (code "62") (name "unconnected-(U3-Pad5)") (class "Default")
      (node (ref "U3") (pin "5") (pintype "passive+no_connect"))
    )
    (net (code "63") (name "unconnected-(U3-Pad6)") (class "Default")
      (node (ref "U3") (pin "6") (pintype "passive+no_connect"))
    )
    (net (code "64") (name "unconnected-(U3-Pad7)") (class "Default")
      (node (ref "U3") (pin "7") (pintype "passive+no_connect"))
    )
    (net (code "65") (name "unconnected-(U4-AREF-Pad21)") (class "Default")
      (node (ref "U4") (pin "21") (pinfunction "AREF_21") (pintype "passive+no_connect"))
    )
    (net (code "66") (name "unconnected-(U4-AVCC-Pad20)") (class "Default")
      (node (ref "U4") (pin "20") (pinfunction "AVCC_20") (pintype "power_in+no_connect"))
    )
    (net (code "67") (name "unconnected-(U4-PB7_(XTAL2{slash}TOSC2)-Pad10)") (class "Default")
      (node (ref "U4") (pin "10") (pinfunction "PB7_(XTAL2/TOSC2)_10") (pintype "bidirectional+no_connect"))
    )
    (net (code "68") (name "unconnected-(U4-PD4_(XCK{slash}T0)-Pad6)") (class "Default")
      (node (ref "U4") (pin "6") (pinfunction "PD4_(XCK/T0)_6") (pintype "bidirectional+no_connect"))
    )
    (net (code "69") (name "unconnected-(U4-PD5_(T1)-Pad11)") (class "Default")
      (node (ref "U4") (pin "11") (pinfunction "PD5_(T1)_11") (pintype "bidirectional+no_connect"))
    )
    (net (code "70") (name "unconnected-(U4-PD6_(AIN0)-Pad12)") (class "Default")
      (node (ref "U4") (pin "12") (pinfunction "PD6_(AIN0)_12") (pintype "bidirectional+no_connect"))
    )
    (net (code "71") (name "unconnected-(U4-PD7_(AIN1)-Pad13)") (class "Default")
      (node (ref "U4") (pin "13") (pinfunction "PD7_(AIN1)_13") (pintype "bidirectional+no_connect"))
    )
  )
)
